# MCU.net
KiCad netlist of a schematic drawn in Altium Designer
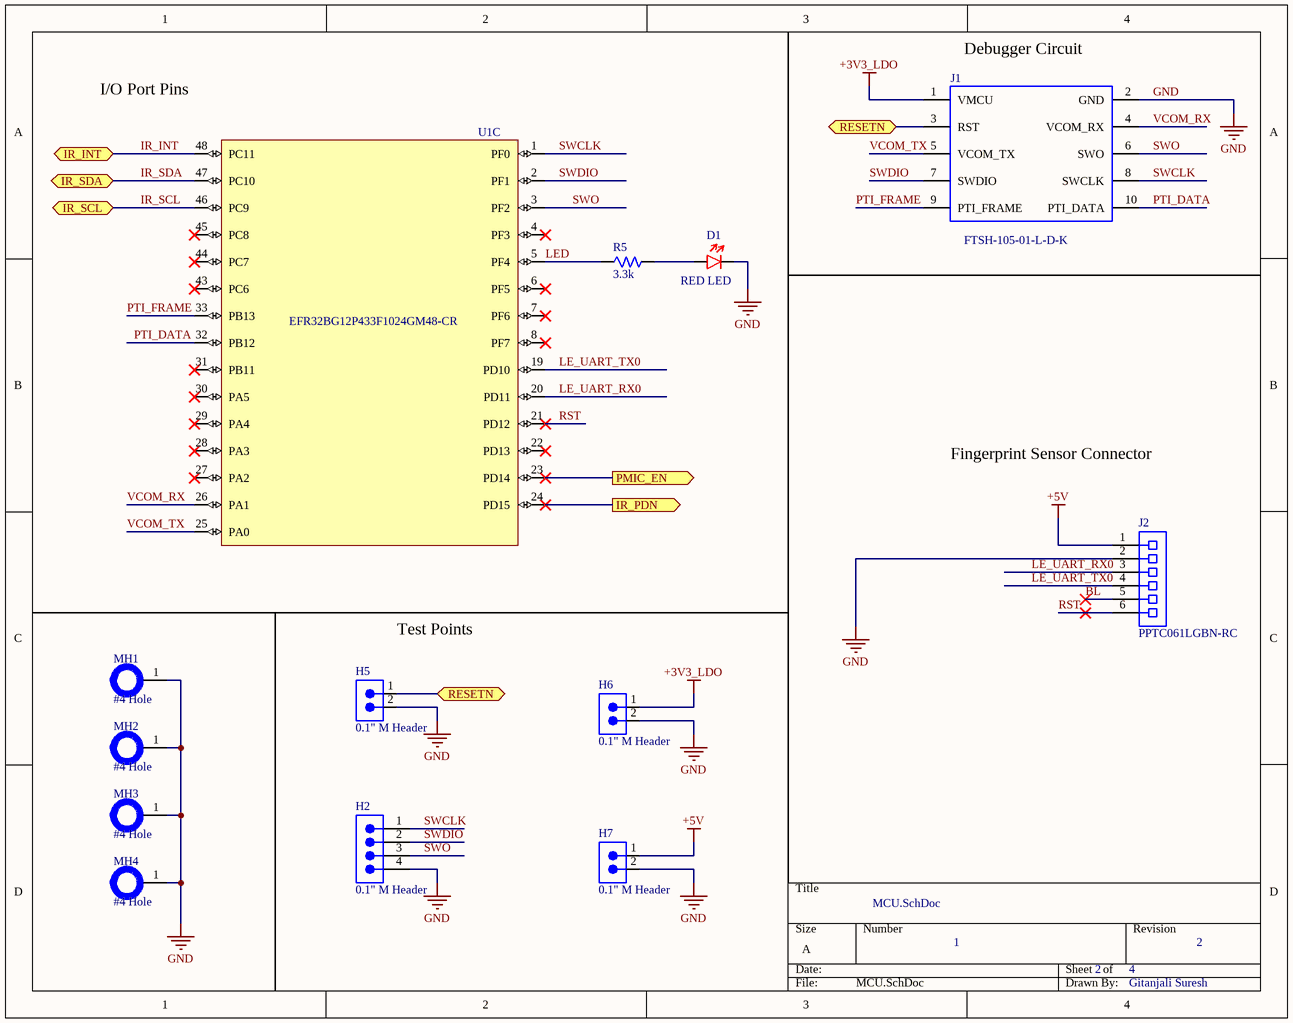
[diagram p0: MCU.SchDoc]

(export (version "E")
  (design (tool "Eeschema 10.0.6"))
  (components
    (comp (ref "D1")
      (value "RED LED")
      (footprint "LED_0603_GRN_WL-SMCW")
      (description "LED LUXEON CZ RED SMD")
      (fields
        (field (name "MANUFACTURER") "Wurth Electronics")
        (field (name "MANUFACTURER PART NUMBER") "150060GS75000")
      )
      (libsource (lib "PMIC_IR") (part "L1CU-RED1000000000"))
    )
    (comp (ref "H2")
      (value "0.1\" M Header")
      (footprint "4-PIN_MALE_HEADER_01-IN")
      (description "CONN HEADER VERT 4POS 2.54MM")
      (fields
        (field (name "MANUFACTURER") "Sullins")
        (field (name "MANUFACTURER PART NUMBER") "PRPC004SAAN-RC")
      )
      (libsource (lib "PMIC_IR") (part "PRPC004SAAN-RC"))
    )
    (comp (ref "H5")
      (value "0.1\" M Header")
      (footprint "77311-118-02LF_AMP")
      (description "Test point")
      (fields
        (field (name "MANUFACTURER") "Amphenol ICC / FCI")
        (field (name "MANUFACTURER PART NUMBER") "77311-118-02LF")
      )
      (libsource (lib "PMIC_IR") (part "77311-118-02LF"))
    )
    (comp (ref "H6")
      (value "0.1\" M Header")
      (footprint "77311-118-02LF_AMP")
      (description "Test point")
      (fields
        (field (name "MANUFACTURER") "Amphenol ICC / FCI")
        (field (name "MANUFACTURER PART NUMBER") "77311-118-02LF")
      )
      (libsource (lib "PMIC_IR") (part "77311-118-02LF"))
    )
    (comp (ref "H7")
      (value "0.1\" M Header")
      (footprint "77311-118-02LF_AMP")
      (description "Test point")
      (fields
        (field (name "MANUFACTURER") "Amphenol ICC / FCI")
        (field (name "MANUFACTURER PART NUMBER") "77311-118-02LF")
      )
      (libsource (lib "PMIC_IR") (part "77311-118-02LF"))
    )
    (comp (ref "J1")
      (value "FTSH-105-01-L-D-K")
      (footprint "SAMTEC_FTSH-105-01-L-D-K")
      (fields (field (name "MANUFACTURER") "Samtec"))
      (libsource (lib "PMIC_IR") (part "FTSH-105-01-L-D-K"))
    )
    (comp (ref "J2")
      (value "PPTC061LGBN-RC")
      (footprint "SAMTEC-SSQ-106-02-X-S-RA")
      (description "Conn Socket Strip SKT 6 POS 2.54mm Solder RA SMD Automotive Tube")
      (fields (field (name "MANUFACTURER") "Samtec") (field (name "MANUFACTURER PART NUMBER") "SSM-106-L-SH"))
      (libsource (lib "PMIC_IR") (part "PPTC061LGBN-RC"))
    )
    (comp (ref "MH1") (value "#4 Hole") (footprint "HOLE_#4") (libsource (lib "PMIC_IR") (part "HOLE_#4")))
    (comp (ref "MH2") (value "#4 Hole") (footprint "HOLE_#4") (libsource (lib "PMIC_IR") (part "HOLE_#4")))
    (comp (ref "MH3") (value "#4 Hole") (footprint "HOLE_#4") (libsource (lib "PMIC_IR") (part "HOLE_#4")))
    (comp (ref "MH4") (value "#4 Hole") (footprint "HOLE_#4") (libsource (lib "PMIC_IR") (part "HOLE_#4")))
    (comp (ref "R5")
      (value "3.3k")
      (footprint "RES_0603_3.3k")
      (description "RES SMD 3.3 KOHM 1% 0.3W 0603")
      (fields
        (field (name "MANUFACTURER") "Yageo")
        (field (name "MANUFACTURER PART NUMBER") "RC0201FR-07100RL")
      )
      (libsource (lib "PMIC_IR") (part "SDR03EZPF3301"))
    )
    (comp (ref "U1")
      (value "EFR32BG12P433F1024GM48-CR")
      (footprint "QFN50P700X700X90_HS-49N")
      (description "Blue Gecko EFR32BG13")
      (fields (field (name "MANUFACTURER") "Silicon Labs"))
      (libsource (lib "PMIC_IR") (part "EFR32BG12P433F1024GM48-CR"))
    )
  )
  (nets
    (net (code "1") (name "+3V3_LDO") (class "Default")
      (node (ref "H6") (pin "1") (pinfunction "1_1") (pintype "passive"))
      (node (ref "J1") (pin "1") (pinfunction "VMCU_1") (pintype "passive"))
    )
    (net (code "2") (name "+5V") (class "Default")
      (node (ref "H7") (pin "1") (pinfunction "1_1") (pintype "passive"))
      (node (ref "J2") (pin "1") (pinfunction "VCC_1") (pintype "passive"))
    )
    (net (code "3") (name "/BL") (class "Default")
      (node (ref "J2") (pin "5") (pinfunction "BL_5") (pintype "passive+no_connect"))
    )
    (net (code "4") (name "/IR_INT") (class "Default")
      (node (ref "U1") (pin "48") (pinfunction "PC11_48") (pintype "bidirectional"))
    )
    (net (code "5") (name "/IR_PDN") (class "Default")
      (node (ref "U1") (pin "24") (pinfunction "PD15_24") (pintype "bidirectional+no_connect"))
    )
    (net (code "6") (name "/IR_SCL") (class "Default")
      (node (ref "U1") (pin "46") (pinfunction "PC9_46") (pintype "bidirectional"))
    )
    (net (code "7") (name "/IR_SDA") (class "Default")
      (node (ref "U1") (pin "47") (pinfunction "PC10_47") (pintype "bidirectional"))
    )
    (net (code "8") (name "/LED") (class "Default")
      (node (ref "R5") (pin "1") (pinfunction "1_1") (pintype "passive"))
      (node (ref "U1") (pin "5") (pinfunction "PF4_5") (pintype "bidirectional"))
    )
    (net (code "9") (name "/LE_UART_RX0") (class "Default")
      (node (ref "J2") (pin "3") (pinfunction "TXD_3") (pintype "passive"))
      (node (ref "U1") (pin "20") (pinfunction "PD11_20") (pintype "bidirectional"))
    )
    (net (code "10") (name "/LE_UART_TX0") (class "Default")
      (node (ref "J2") (pin "4") (pinfunction "RXD_4") (pintype "passive"))
      (node (ref "U1") (pin "19") (pinfunction "PD10_19") (pintype "bidirectional"))
    )
    (net (code "11") (name "/PMIC_EN") (class "Default")
      (node (ref "U1") (pin "23") (pinfunction "PD14_23") (pintype "bidirectional+no_connect"))
    )
    (net (code "12") (name "/PTI_DATA") (class "Default")
      (node (ref "J1") (pin "10") (pinfunction "PTI_DATA_10") (pintype "passive"))
      (node (ref "U1") (pin "32") (pinfunction "PB12_32") (pintype "bidirectional"))
    )
    (net (code "13") (name "/PTI_FRAME") (class "Default")
      (node (ref "J1") (pin "9") (pinfunction "PTI_FRAME_9") (pintype "passive"))
      (node (ref "U1") (pin "33") (pinfunction "PB13_33") (pintype "bidirectional"))
    )
    (net (code "14") (name "/RESETN") (class "Default")
      (node (ref "H5") (pin "1") (pinfunction "1_1") (pintype "passive"))
      (node (ref "J1") (pin "3") (pinfunction "RST_3") (pintype "passive"))
    )
    (net (code "15") (name "/RST") (class "Default")
      (node (ref "J2") (pin "6") (pinfunction "RST_6") (pintype "passive"))
      (node (ref "U1") (pin "21") (pinfunction "PD12_21") (pintype "bidirectional"))
    )
    (net (code "16") (name "/SWCLK") (class "Default")
      (node (ref "H2") (pin "1") (pinfunction "1_1") (pintype "passive"))
      (node (ref "J1") (pin "8") (pinfunction "SWCLK_8") (pintype "passive"))
      (node (ref "U1") (pin "1") (pinfunction "PF0_1") (pintype "bidirectional"))
    )
    (net (code "17") (name "/SWDIO") (class "Default")
      (node (ref "H2") (pin "2") (pinfunction "2_2") (pintype "passive"))
      (node (ref "J1") (pin "7") (pinfunction "SWDIO_7") (pintype "passive"))
      (node (ref "U1") (pin "2") (pinfunction "PF1_2") (pintype "bidirectional"))
    )
    (net (code "18") (name "/SWO") (class "Default")
      (node (ref "H2") (pin "3") (pinfunction "3_3") (pintype "passive"))
      (node (ref "J1") (pin "6") (pinfunction "SWO_6") (pintype "passive"))
      (node (ref "U1") (pin "3") (pinfunction "PF2_3") (pintype "bidirectional"))
    )
    (net (code "19") (name "/VCOM_RX") (class "Default")
      (node (ref "J1") (pin "4") (pinfunction "VCOM_RX_4") (pintype "passive"))
      (node (ref "U1") (pin "26") (pinfunction "PA1_26") (pintype "bidirectional"))
    )
    (net (code "20") (name "/VCOM_TX") (class "Default")
      (node (ref "J1") (pin "5") (pinfunction "VCOM_TX_5") (pintype "passive"))
      (node (ref "U1") (pin "25") (pinfunction "PA0_25") (pintype "bidirectional"))
    )
    (net (code "21") (name "GND") (class "Default")
      (node (ref "D1") (pin "2") (pinfunction "2_2") (pintype "passive"))
      (node (ref "H2") (pin "4") (pinfunction "4_4") (pintype "passive"))
      (node (ref "H5") (pin "2") (pinfunction "1_2") (pintype "passive"))
      (node (ref "H6") (pin "2") (pinfunction "1_2") (pintype "passive"))
      (node (ref "H7") (pin "2") (pinfunction "1_2") (pintype "passive"))
      (node (ref "J1") (pin "2") (pinfunction "GND_2") (pintype "passive"))
      (node (ref "J2") (pin "2") (pinfunction "GND_2") (pintype "passive"))
      (node (ref "MH1") (pin "1") (pinfunction "1_1") (pintype "passive"))
      (node (ref "MH2") (pin "1") (pinfunction "1_1") (pintype "passive"))
      (node (ref "MH3") (pin "1") (pinfunction "1_1") (pintype "passive"))
      (node (ref "MH4") (pin "1") (pinfunction "1_1") (pintype "passive"))
    )
    (net (code "22") (name "Net-(D1-Pad1)") (class "Default")
      (node (ref "D1") (pin "1") (pinfunction "1_1") (pintype "passive"))
      (node (ref "R5") (pin "2") (pinfunction "2_2") (pintype "passive"))
    )
    (net (code "23") (name "unconnected-(U1C-PA2-Pad27)") (class "Default")
      (node (ref "U1") (pin "27") (pinfunction "PA2_27") (pintype "bidirectional+no_connect"))
    )
    (net (code "24") (name "unconnected-(U1C-PA3-Pad28)") (class "Default")
      (node (ref "U1") (pin "28") (pinfunction "PA3_28") (pintype "bidirectional+no_connect"))
    )
    (net (code "25") (name "unconnected-(U1C-PA4-Pad29)") (class "Default")
      (node (ref "U1") (pin "29") (pinfunction "PA4_29") (pintype "bidirectional+no_connect"))
    )
    (net (code "26") (name "unconnected-(U1C-PA5-Pad30)") (class "Default")
      (node (ref "U1") (pin "30") (pinfunction "PA5_30") (pintype "bidirectional+no_connect"))
    )
    (net (code "27") (name "unconnected-(U1C-PB11-Pad31)") (class "Default")
      (node (ref "U1") (pin "31") (pinfunction "PB11_31") (pintype "bidirectional+no_connect"))
    )
    (net (code "28") (name "unconnected-(U1C-PC6-Pad43)") (class "Default")
      (node (ref "U1") (pin "43") (pinfunction "PC6_43") (pintype "bidirectional+no_connect"))
    )
    (net (code "29") (name "unconnected-(U1C-PC7-Pad44)") (class "Default")
      (node (ref "U1") (pin "44") (pinfunction "PC7_44") (pintype "bidirectional+no_connect"))
    )
    (net (code "30") (name "unconnected-(U1C-PC8-Pad45)") (class "Default")
      (node (ref "U1") (pin "45") (pinfunction "PC8_45") (pintype "bidirectional+no_connect"))
    )
    (net (code "31") (name "unconnected-(U1C-PD13-Pad22)") (class "Default")
      (node (ref "U1") (pin "22") (pinfunction "PD13_22") (pintype "bidirectional+no_connect"))
    )
    (net (code "32") (name "unconnected-(U1C-PF3-Pad4)") (class "Default")
      (node (ref "U1") (pin "4") (pinfunction "PF3_4") (pintype "bidirectional+no_connect"))
    )
    (net (code "33") (name "unconnected-(U1C-PF5-Pad6)") (class "Default")
      (node (ref "U1") (pin "6") (pinfunction "PF5_6") (pintype "bidirectional+no_connect"))
    )
    (net (code "34") (name "unconnected-(U1C-PF6-Pad7)") (class "Default")
      (node (ref "U1") (pin "7") (pinfunction "PF6_7") (pintype "bidirectional+no_connect"))
    )
    (net (code "35") (name "unconnected-(U1C-PF7-Pad8)") (class "Default")
      (node (ref "U1") (pin "8") (pinfunction "PF7_8") (pintype "bidirectional+no_connect"))
    )
  )
)
